# Battery_Monitoring_V3.net
KiCad netlist of a schematic drawn in EAGLE
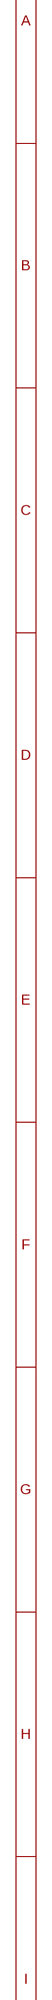
[diagram p0: schematic, sheet 1, part 1 of 2]
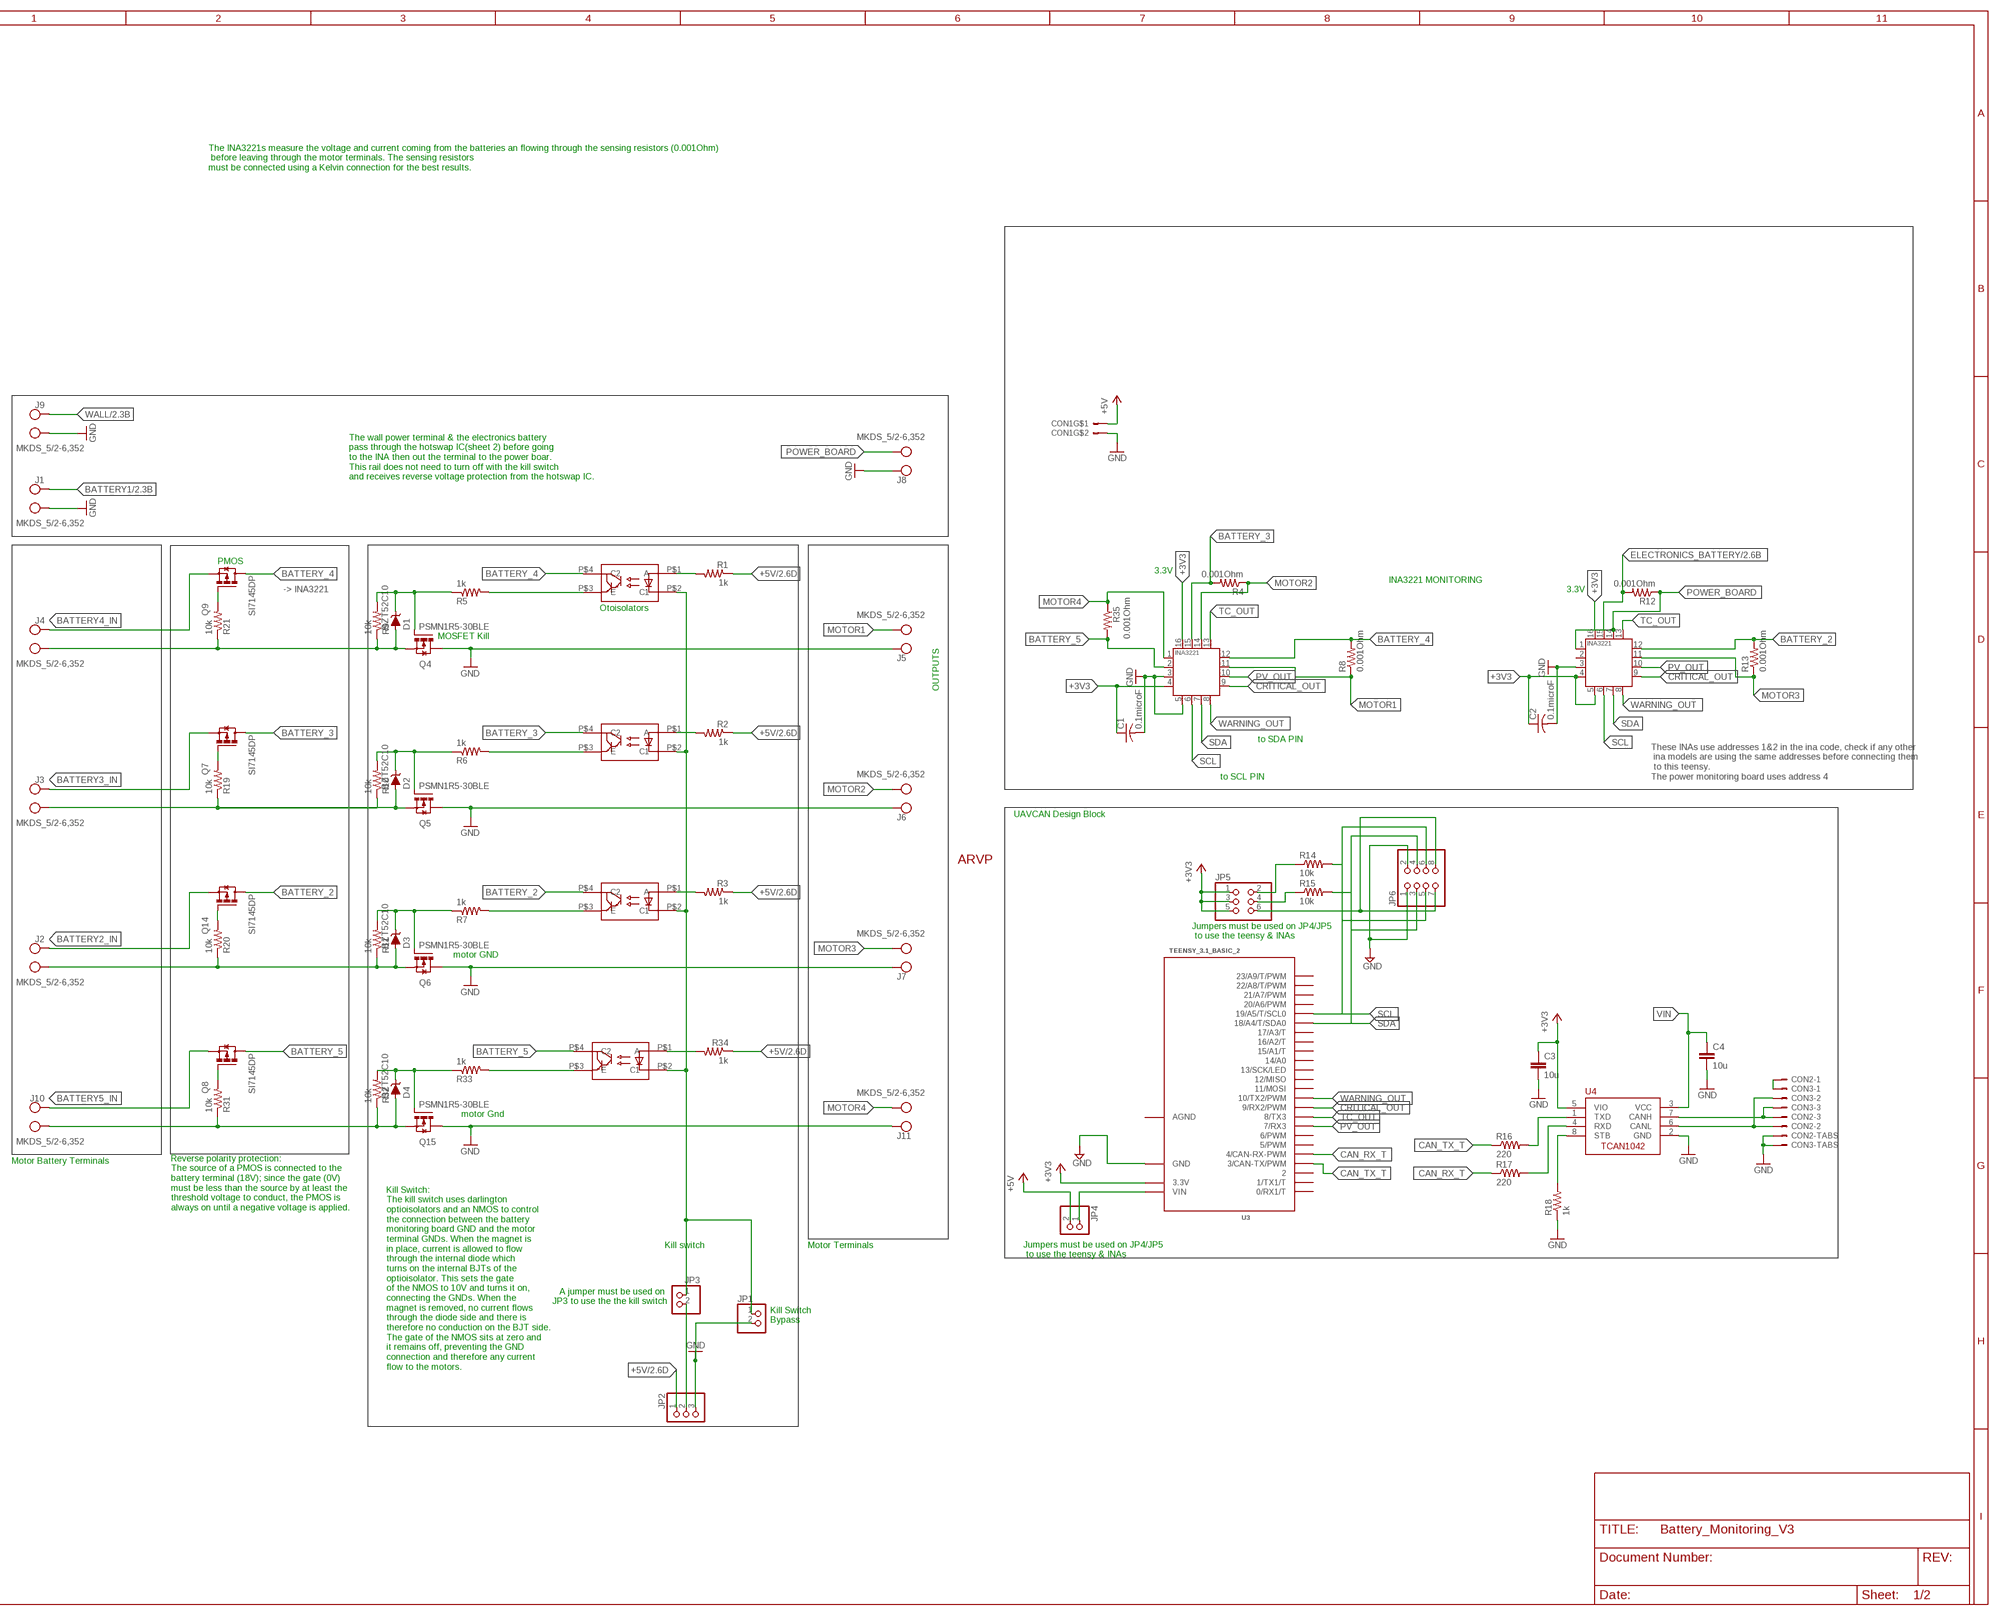
[diagram p1: schematic, sheet 1, part 2 of 2]
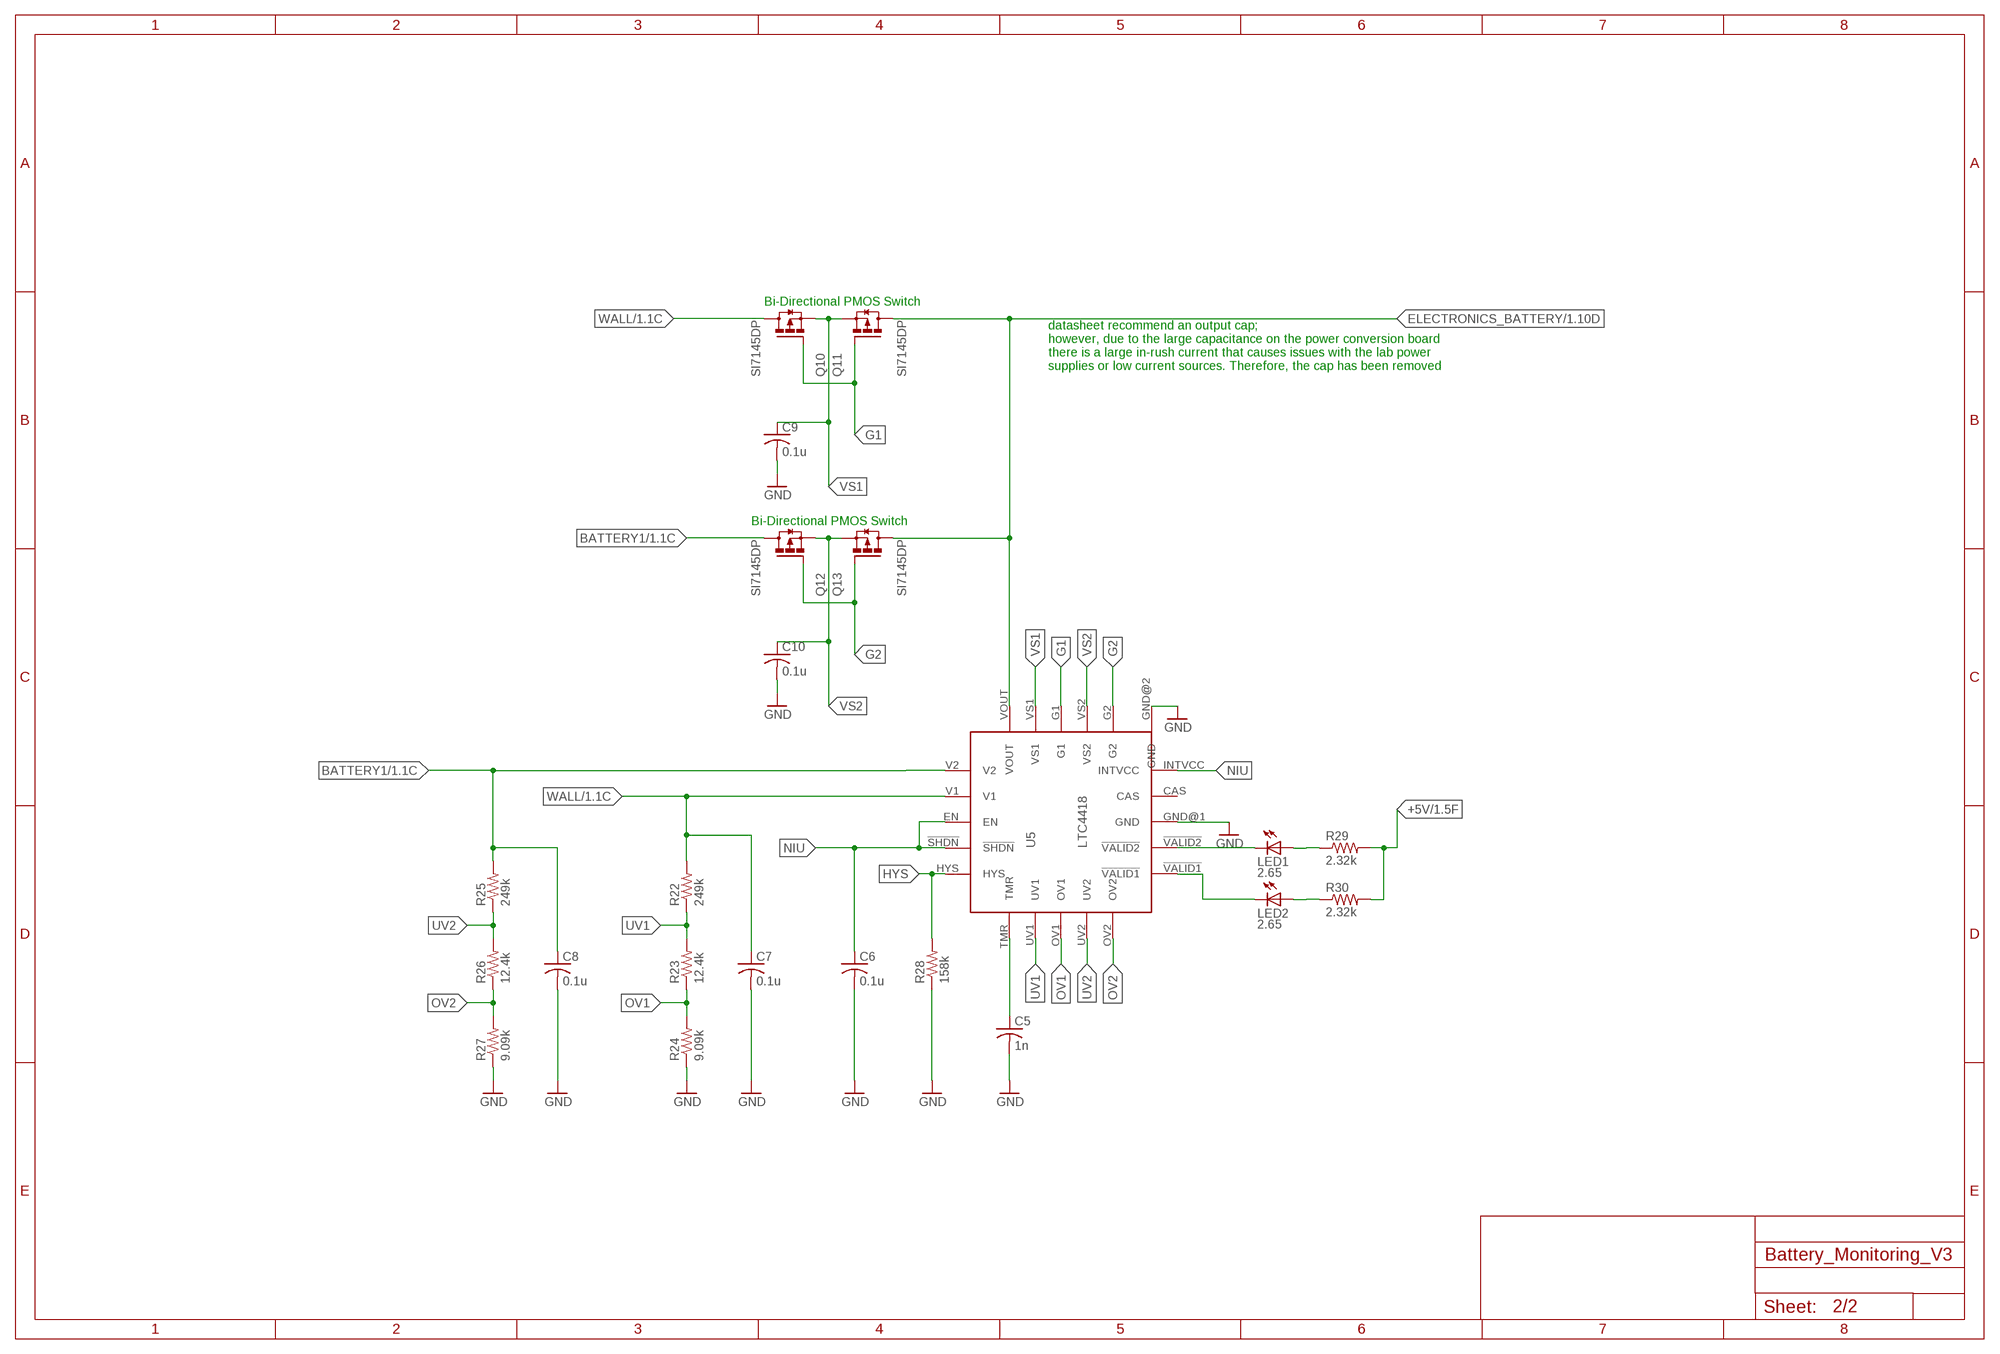
[diagram p2: schematic, sheet 2]

(export (version "E")
  (design (tool "Eeschema 10.0.6"))
  (components
    (comp (ref "ARVP1")
      (value "ARVP_LOGO")
      (footprint "eagle-import:ARVP")
      (libsource (lib "eagle-import") (part "ARVP_LOGO"))
    )
    (comp (ref "C1")
      (value "0.1microF")
      (footprint "eagle-import:C2012")
      (libsource (lib "eagle-import") (part "resistor_348_C-USC2012"))
    )
    (comp (ref "C2")
      (value "0.1microF")
      (footprint "eagle-import:C2012")
      (libsource (lib "eagle-import") (part "resistor_348_C-USC2012"))
    )
    (comp (ref "C3")
      (value "10u")
      (footprint "eagle-import:C0805")
      (libsource (lib "eagle-import") (part "C-EUC0805"))
    )
    (comp (ref "C4")
      (value "10u")
      (footprint "eagle-import:C0805")
      (libsource (lib "eagle-import") (part "C-EUC0805"))
    )
    (comp (ref "CON1")
      (value "MOLEX_5566-2")
      (footprint "eagle-import:5566-2")
      (libsource (lib "eagle-import") (part "MOLEX_5566-2"))
    )
    (comp (ref "CON2")
      (value "SM03B-GHS-TB")
      (footprint "eagle-import:SM03B-GHS-TB")
      (libsource (lib "eagle-import") (part "SM03B-GHS-TB"))
    )
    (comp (ref "CON3")
      (value "SM03B-GHS-TB")
      (footprint "eagle-import:SM03B-GHS-TB")
      (libsource (lib "eagle-import") (part "SM03B-GHS-TB"))
    )
    (comp (ref "D1")
      (value "BZT52C10")
      (footprint "eagle-import:SOD-123")
      (libsource (lib "eagle-import") (part "BZT52C10"))
    )
    (comp (ref "D2")
      (value "BZT52C10")
      (footprint "eagle-import:SOD-123")
      (libsource (lib "eagle-import") (part "BZT52C10"))
    )
    (comp (ref "D3")
      (value "BZT52C10")
      (footprint "eagle-import:SOD-123")
      (libsource (lib "eagle-import") (part "BZT52C10"))
    )
    (comp (ref "D4")
      (value "BZT52C10")
      (footprint "eagle-import:SOD-123")
      (libsource (lib "eagle-import") (part "BZT52C10"))
    )
    (comp (ref "J1")
      (value "MKDS_5/2-6,352")
      (footprint "eagle-import:MKDS_5_2-6,35")
      (libsource (lib "eagle-import") (part "MKDS_5/2-6,352"))
    )
    (comp (ref "J2")
      (value "MKDS_5/2-6,352")
      (footprint "eagle-import:MKDS_5_2-6,35")
      (libsource (lib "eagle-import") (part "MKDS_5/2-6,352"))
    )
    (comp (ref "J3")
      (value "MKDS_5/2-6,352")
      (footprint "eagle-import:MKDS_5_2-6,35")
      (libsource (lib "eagle-import") (part "MKDS_5/2-6,352"))
    )
    (comp (ref "J4")
      (value "MKDS_5/2-6,352")
      (footprint "eagle-import:MKDS_5_2-6,35")
      (libsource (lib "eagle-import") (part "MKDS_5/2-6,352"))
    )
    (comp (ref "J5")
      (value "MKDS_5/2-6,352")
      (footprint "eagle-import:MKDS_5_2-6,35")
      (libsource (lib "eagle-import") (part "MKDS_5/2-6,352"))
    )
    (comp (ref "J6")
      (value "MKDS_5/2-6,352")
      (footprint "eagle-import:MKDS_5_2-6,35")
      (libsource (lib "eagle-import") (part "MKDS_5/2-6,352"))
    )
    (comp (ref "J7")
      (value "MKDS_5/2-6,352")
      (footprint "eagle-import:MKDS_5_2-6,35")
      (libsource (lib "eagle-import") (part "MKDS_5/2-6,352"))
    )
    (comp (ref "J8")
      (value "MKDS_5/2-6,352")
      (footprint "eagle-import:MKDS_5_2-6,35")
      (libsource (lib "eagle-import") (part "MKDS_5/2-6,352"))
    )
    (comp (ref "J9")
      (value "MKDS_5/2-6,352")
      (footprint "eagle-import:MKDS_5_2-6,35")
      (libsource (lib "eagle-import") (part "MKDS_5/2-6,352"))
    )
    (comp (ref "J10")
      (value "MKDS_5/2-6,352")
      (footprint "eagle-import:MKDS_5_2-6,35")
      (libsource (lib "eagle-import") (part "MKDS_5/2-6,352"))
    )
    (comp (ref "J11")
      (value "MKDS_5/2-6,352")
      (footprint "eagle-import:MKDS_5_2-6,35")
      (libsource (lib "eagle-import") (part "MKDS_5/2-6,352"))
    )
    (comp (ref "JP1")
      (value "PINHD-1X2")
      (footprint "eagle-import:1X02")
      (libsource (lib "eagle-import") (part "PINHD-1X2"))
    )
    (comp (ref "JP2")
      (value "PINHD-1X3")
      (footprint "eagle-import:1X03")
      (libsource (lib "eagle-import") (part "PINHD-1X3"))
    )
    (comp (ref "JP3")
      (value "PINHD-1X2")
      (footprint "eagle-import:1X02")
      (libsource (lib "eagle-import") (part "PINHD-1X2"))
    )
    (comp (ref "JP4")
      (value "PINHD-1X2")
      (footprint "eagle-import:1X02")
      (libsource (lib "eagle-import") (part "PINHD-1X2"))
    )
    (comp (ref "JP5")
      (value "PINHD-2X3")
      (footprint "eagle-import:2X03")
      (libsource (lib "eagle-import") (part "PINHD-2X3"))
    )
    (comp (ref "JP6")
      (value "PINHD-2X4")
      (footprint "eagle-import:2X04")
      (libsource (lib "eagle-import") (part "PINHD-2X4"))
    )
    (comp (ref "Q1")
      (value "TCLD1000CT")
      (footprint "eagle-import:SOP-4L")
      (fields (field (name "SPICEPREFIX") "E"))
      (libsource (lib "eagle-import") (part "TCLD1000CT"))
    )
    (comp (ref "Q2")
      (value "TCLD1000CT")
      (footprint "eagle-import:SOP-4L")
      (libsource (lib "eagle-import") (part "TCLD1000CT"))
    )
    (comp (ref "Q3")
      (value "TCLD1000CT")
      (footprint "eagle-import:SOP-4L")
      (libsource (lib "eagle-import") (part "TCLD1000CT"))
    )
    (comp (ref "Q4")
      (value "PSMN1R5-30BLE")
      (footprint "eagle-import:SOT404_D2PAK")
      (libsource (lib "eagle-import") (part "PSMN1R5-30BLE"))
    )
    (comp (ref "Q5")
      (value "PSMN1R5-30BLE")
      (footprint "eagle-import:SOT404_D2PAK")
      (libsource (lib "eagle-import") (part "PSMN1R5-30BLE"))
    )
    (comp (ref "Q6")
      (value "PSMN1R5-30BLE")
      (footprint "eagle-import:SOT404_D2PAK")
      (libsource (lib "eagle-import") (part "PSMN1R5-30BLE"))
    )
    (comp (ref "Q7")
      (value "SI7145DP")
      (footprint "eagle-import:SO-8_PPAK_TEST")
      (fields (field (name "MPN") "SI7145DP-T1-GE3"))
      (libsource (lib "eagle-import") (part "Si7145DP_SI7145DP"))
    )
    (comp (ref "Q8")
      (value "SI7145DP")
      (footprint "eagle-import:SO-8_PPAK_TEST")
      (fields (field (name "MPN") "SI7145DP-T1-GE3"))
      (libsource (lib "eagle-import") (part "Si7145DP_SI7145DP"))
    )
    (comp (ref "Q9")
      (value "SI7145DP")
      (footprint "eagle-import:SO-8_PPAK_TEST")
      (fields (field (name "MPN") "SI7145DP-T1-GE3"))
      (libsource (lib "eagle-import") (part "Si7145DP_SI7145DP"))
    )
    (comp (ref "Q14")
      (value "SI7145DP")
      (footprint "eagle-import:SO-8_PPAK_TEST")
      (fields (field (name "MPN") "SI7145DP-T1-GE3"))
      (libsource (lib "eagle-import") (part "Si7145DP_SI7145DP"))
    )
    (comp (ref "Q15")
      (value "PSMN1R5-30BLE")
      (footprint "eagle-import:SOT404_D2PAK")
      (libsource (lib "eagle-import") (part "PSMN1R5-30BLE"))
    )
    (comp (ref "Q16")
      (value "TCLD1000CT")
      (footprint "eagle-import:SOP-4L")
      (libsource (lib "eagle-import") (part "TCLD1000CT"))
    )
    (comp (ref "R1")
      (value "1k")
      (footprint "eagle-import:R0805")
      (libsource (lib "eagle-import") (part "adafruit_420_R-US_R0805"))
    )
    (comp (ref "R2")
      (value "1k")
      (footprint "eagle-import:R0805")
      (libsource (lib "eagle-import") (part "adafruit_420_R-US_R0805"))
    )
    (comp (ref "R3")
      (value "1k")
      (footprint "eagle-import:R0805")
      (libsource (lib "eagle-import") (part "adafruit_420_R-US_R0805"))
    )
    (comp (ref "R4")
      (value "0.001Ohm")
      (footprint "eagle-import:3920")
      (libsource (lib "eagle-import") (part "HCS3920FT1L00"))
    )
    (comp (ref "R5")
      (value "1k")
      (footprint "eagle-import:M1206")
      (libsource (lib "eagle-import") (part "adafruit_420_R-US_M1206"))
    )
    (comp (ref "R6")
      (value "1k")
      (footprint "eagle-import:M1206")
      (libsource (lib "eagle-import") (part "adafruit_420_R-US_M1206"))
    )
    (comp (ref "R7")
      (value "1k")
      (footprint "eagle-import:M1206")
      (libsource (lib "eagle-import") (part "adafruit_420_R-US_M1206"))
    )
    (comp (ref "R8")
      (value "0.001Ohm")
      (footprint "eagle-import:3920")
      (libsource (lib "eagle-import") (part "HCS3920FT1L00"))
    )
    (comp (ref "R9")
      (value "10k")
      (footprint "eagle-import:M1206")
      (libsource (lib "eagle-import") (part "adafruit_420_R-US_M1206"))
    )
    (comp (ref "R10")
      (value "10k")
      (footprint "eagle-import:M1206")
      (libsource (lib "eagle-import") (part "adafruit_420_R-US_M1206"))
    )
    (comp (ref "R11")
      (value "10k")
      (footprint "eagle-import:M1206")
      (libsource (lib "eagle-import") (part "adafruit_420_R-US_M1206"))
    )
    (comp (ref "R12")
      (value "0.001Ohm")
      (footprint "eagle-import:3920")
      (libsource (lib "eagle-import") (part "HCS3920FT1L00"))
    )
    (comp (ref "R13")
      (value "0.001Ohm")
      (footprint "eagle-import:3920")
      (libsource (lib "eagle-import") (part "HCS3920FT1L00"))
    )
    (comp (ref "R14")
      (value "10k")
      (footprint "eagle-import:R1206")
      (libsource (lib "eagle-import") (part "rcl_334_R-US_R1206"))
    )
    (comp (ref "R15")
      (value "10k")
      (footprint "eagle-import:R1206")
      (libsource (lib "eagle-import") (part "rcl_334_R-US_R1206"))
    )
    (comp (ref "R16")
      (value "220")
      (footprint "eagle-import:R0805")
      (libsource (lib "eagle-import") (part "rcl_334_R-US_R0805"))
    )
    (comp (ref "R17")
      (value "220")
      (footprint "eagle-import:R0805")
      (libsource (lib "eagle-import") (part "rcl_334_R-US_R0805"))
    )
    (comp (ref "R18")
      (value "1k")
      (footprint "eagle-import:R0805")
      (libsource (lib "eagle-import") (part "rcl_334_R-US_R0805"))
    )
    (comp (ref "R19")
      (value "10k")
      (footprint "eagle-import:M1206")
      (fields (field (name "MPN") "RC0603FR-0710KL"))
      (libsource (lib "eagle-import") (part "R-US_M1206"))
    )
    (comp (ref "R20")
      (value "10k")
      (footprint "eagle-import:M1206")
      (fields (field (name "MPN") "RC0603FR-0710KL"))
      (libsource (lib "eagle-import") (part "R-US_M1206"))
    )
    (comp (ref "R21")
      (value "10k")
      (footprint "eagle-import:M1206")
      (fields (field (name "MPN") "RC0603FR-0710KL"))
      (libsource (lib "eagle-import") (part "adafruit_420_R-US_M1206"))
    )
    (comp (ref "R31")
      (value "10k")
      (footprint "eagle-import:M1206")
      (fields (field (name "MPN") "RC0603FR-0710KL"))
      (libsource (lib "eagle-import") (part "R-US_M1206"))
    )
    (comp (ref "R32")
      (value "10k")
      (footprint "eagle-import:M1206")
      (libsource (lib "eagle-import") (part "adafruit_420_R-US_M1206"))
    )
    (comp (ref "R33")
      (value "1k")
      (footprint "eagle-import:M1206")
      (libsource (lib "eagle-import") (part "adafruit_420_R-US_M1206"))
    )
    (comp (ref "R34")
      (value "1k")
      (footprint "eagle-import:R0805")
      (libsource (lib "eagle-import") (part "adafruit_420_R-US_R0805"))
    )
    (comp (ref "R35")
      (value "0.001Ohm")
      (footprint "eagle-import:3920")
      (libsource (lib "eagle-import") (part "HCS3920FT1L00"))
    )
    (comp (ref "U1")
      (value "INA3221.")
      (footprint "eagle-import:HVQFN16_4X4")
      (libsource (lib "eagle-import") (part "INA3221."))
    )
    (comp (ref "U2")
      (value "INA3221.")
      (footprint "eagle-import:HVQFN16_4X4")
      (libsource (lib "eagle-import") (part "INA3221."))
    )
    (comp (ref "U3")
      (value "TEENSY_3.1_BASIC_2")
      (footprint "eagle-import:TEENSY_3.1_BASIC_2")
      (libsource (lib "eagle-import") (part "TEENSY_3.1_BASIC_2"))
    )
    (comp (ref "U4")
      (value "TCAN1042HVDR")
      (footprint "eagle-import:SO-8")
      (libsource (lib "eagle-import") (part "TCAN1042HVDR"))
    )
    (comp (ref "C5")
      (value "1n")
      (footprint "eagle-import:C0805")
      (libsource (lib "eagle-import") (part "C-USC0805"))
    )
    (comp (ref "C6")
      (value "0.1u")
      (footprint "eagle-import:C0805")
      (libsource (lib "eagle-import") (part "C-USC0805"))
    )
    (comp (ref "C7")
      (value "0.1u")
      (footprint "eagle-import:C0805")
      (libsource (lib "eagle-import") (part "C-USC0805"))
    )
    (comp (ref "C8")
      (value "0.1u")
      (footprint "eagle-import:C0805")
      (libsource (lib "eagle-import") (part "C-USC0805"))
    )
    (comp (ref "C9")
      (value "0.1u")
      (footprint "eagle-import:C0805")
      (libsource (lib "eagle-import") (part "C-USC0805"))
    )
    (comp (ref "C10")
      (value "0.1u")
      (footprint "eagle-import:C0805")
      (libsource (lib "eagle-import") (part "C-USC0805"))
    )
    (comp (ref "LED1")
      (value "2.65")
      (footprint "eagle-import:SML0805")
      (libsource (lib "eagle-import") (part "LEDSML0805"))
    )
    (comp (ref "LED2")
      (value "2.65")
      (footprint "eagle-import:SML0805")
      (libsource (lib "eagle-import") (part "LEDSML0805"))
    )
    (comp (ref "Q10")
      (value "SI7145DP")
      (footprint "eagle-import:SO-8_PPAK_TEST")
      (libsource (lib "eagle-import") (part "SI7145DP"))
    )
    (comp (ref "Q11")
      (value "SI7145DP")
      (footprint "eagle-import:SO-8_PPAK_TEST")
      (libsource (lib "eagle-import") (part "SI7145DP"))
    )
    (comp (ref "Q12")
      (value "SI7145DP")
      (footprint "eagle-import:SO-8_PPAK_TEST")
      (libsource (lib "eagle-import") (part "SI7145DP"))
    )
    (comp (ref "Q13")
      (value "SI7145DP")
      (footprint "eagle-import:SO-8_PPAK_TEST")
      (libsource (lib "eagle-import") (part "SI7145DP"))
    )
    (comp (ref "R22")
      (value "249k")
      (footprint "eagle-import:R1206")
      (libsource (lib "eagle-import") (part "adafruit_420_R-US_R1206"))
    )
    (comp (ref "R23")
      (value "12.4k")
      (footprint "eagle-import:R0805")
      (libsource (lib "eagle-import") (part "adafruit_420_R-US_R0805"))
    )
    (comp (ref "R24")
      (value "9.09k")
      (footprint "eagle-import:R0805")
      (libsource (lib "eagle-import") (part "adafruit_420_R-US_R0805"))
    )
    (comp (ref "R25")
      (value "249k")
      (footprint "eagle-import:R1206")
      (libsource (lib "eagle-import") (part "adafruit_420_R-US_R1206"))
    )
    (comp (ref "R26")
      (value "12.4k")
      (footprint "eagle-import:R0805")
      (libsource (lib "eagle-import") (part "adafruit_420_R-US_R0805"))
    )
    (comp (ref "R27")
      (value "9.09k")
      (footprint "eagle-import:R0805")
      (libsource (lib "eagle-import") (part "adafruit_420_R-US_R0805"))
    )
    (comp (ref "R28")
      (value "158k")
      (footprint "eagle-import:R0805")
      (libsource (lib "eagle-import") (part "adafruit_420_R-US_R0805"))
    )
    (comp (ref "R29")
      (value "2.32k")
      (footprint "eagle-import:R0805")
      (libsource (lib "eagle-import") (part "adafruit_420_R-US_R0805"))
    )
    (comp (ref "R30")
      (value "2.32k")
      (footprint "eagle-import:R0805")
      (libsource (lib "eagle-import") (part "adafruit_420_R-US_R0805"))
    )
    (comp (ref "U5")
      (value "LTC4418")
      (footprint "eagle-import:20-QFN(4X4)")
      (libsource (lib "eagle-import") (part "LTC4418"))
    )
  )
  (nets
    (net (code "1") (name "+3V3") (class "Default")
      (node (ref "C1") (pin "1") (pinfunction "1_1") (pintype "passive"))
      (node (ref "C2") (pin "1") (pinfunction "1_1") (pintype "passive"))
      (node (ref "C3") (pin "1") (pinfunction "1_1") (pintype "passive"))
      (node (ref "JP5") (pin "1") (pinfunction "1_1") (pintype "passive"))
      (node (ref "JP5") (pin "3") (pinfunction "3_3") (pintype "passive"))
      (node (ref "JP5") (pin "5") (pinfunction "5_5") (pintype "passive"))
      (node (ref "U1") (pin "16") (pinfunction "VPU_16") (pintype "input"))
      (node (ref "U1") (pin "4") (pinfunction "VS_4") (pintype "power_in"))
      (node (ref "U2") (pin "16") (pinfunction "VPU_16") (pintype "input"))
      (node (ref "U2") (pin "4") (pinfunction "VS_4") (pintype "power_in"))
      (node (ref "U2") (pin "5") (pinfunction "A0_5") (pintype "input"))
      (node (ref "U3") (pin "3.3V") (pinfunction "3.3V_3.3V") (pintype "power_in"))
      (node (ref "U4") (pin "5") (pinfunction "VIO_5") (pintype "bidirectional"))
    )
    (net (code "2") (name "+5V") (class "Default")
      (node (ref "CON1") (pin "1") (pinfunction "S_1") (pintype "passive"))
      (node (ref "JP2") (pin "1") (pinfunction "1_1") (pintype "passive"))
      (node (ref "JP4") (pin "2") (pinfunction "2_2") (pintype "passive"))
      (node (ref "R1") (pin "1") (pinfunction "1_1") (pintype "passive"))
      (node (ref "R2") (pin "1") (pinfunction "1_1") (pintype "passive"))
      (node (ref "R29") (pin "2") (pinfunction "2_2") (pintype "passive"))
      (node (ref "R3") (pin "1") (pinfunction "1_1") (pintype "passive"))
      (node (ref "R30") (pin "2") (pinfunction "2_2") (pintype "passive"))
      (node (ref "R34") (pin "1") (pinfunction "1_1") (pintype "passive"))
    )
    (net (code "3") (name "AGND") (class "Default")
      (node (ref "U3") (pin "AGND") (pinfunction "AGND_AGND") (pintype "power_in"))
    )
    (net (code "4") (name "BATTERY1") (class "Default")
      (node (ref "C8") (pin "1") (pinfunction "1_1") (pintype "passive"))
      (node (ref "J1") (pin "2") (pinfunction "KL1_2") (pintype "passive"))
      (node (ref "Q12") (pin "D@1") (pinfunction "D_D@1") (pintype "passive"))
      (node (ref "Q12") (pin "D@2") (pinfunction "D_D@2") (pintype "passive"))
      (node (ref "Q12") (pin "D@3") (pinfunction "D_D@3") (pintype "passive"))
      (node (ref "Q12") (pin "D@4") (pinfunction "D_D@4") (pintype "passive"))
      (node (ref "Q12") (pin "D@5") (pinfunction "D_D@5") (pintype "passive"))
      (node (ref "R25") (pin "2") (pinfunction "2_2") (pintype "passive"))
      (node (ref "U5") (pin "V2") (pinfunction "V2_V2") (pintype "bidirectional"))
    )
    (net (code "5") (name "BATTERY2_IN") (class "Default")
      (node (ref "J2") (pin "2") (pinfunction "KL1_2") (pintype "passive"))
      (node (ref "Q14") (pin "S@1") (pinfunction "S_S@1") (pintype "passive"))
      (node (ref "Q14") (pin "S@2") (pinfunction "S_S@2") (pintype "passive"))
      (node (ref "Q14") (pin "S@3") (pinfunction "S_S@3") (pintype "passive"))
    )
    (net (code "6") (name "BATTERY3_IN") (class "Default")
      (node (ref "J3") (pin "2") (pinfunction "KL1_2") (pintype "passive"))
      (node (ref "Q7") (pin "S@1") (pinfunction "S_S@1") (pintype "passive"))
      (node (ref "Q7") (pin "S@2") (pinfunction "S_S@2") (pintype "passive"))
      (node (ref "Q7") (pin "S@3") (pinfunction "S_S@3") (pintype "passive"))
    )
    (net (code "7") (name "BATTERY4_IN") (class "Default")
      (node (ref "J4") (pin "2") (pinfunction "KL1_2") (pintype "passive"))
      (node (ref "Q9") (pin "S@1") (pinfunction "S_S@1") (pintype "passive"))
      (node (ref "Q9") (pin "S@2") (pinfunction "S_S@2") (pintype "passive"))
      (node (ref "Q9") (pin "S@3") (pinfunction "S_S@3") (pintype "passive"))
    )
    (net (code "8") (name "BATTERY5_IN") (class "Default")
      (node (ref "J10") (pin "2") (pinfunction "KL1_2") (pintype "passive"))
      (node (ref "Q8") (pin "S@1") (pinfunction "S_S@1") (pintype "passive"))
      (node (ref "Q8") (pin "S@2") (pinfunction "S_S@2") (pintype "passive"))
      (node (ref "Q8") (pin "S@3") (pinfunction "S_S@3") (pintype "passive"))
    )
    (net (code "9") (name "BATTERY_2") (class "Default")
      (node (ref "Q14") (pin "D@1") (pinfunction "D_D@1") (pintype "passive"))
      (node (ref "Q14") (pin "D@2") (pinfunction "D_D@2") (pintype "passive"))
      (node (ref "Q14") (pin "D@3") (pinfunction "D_D@3") (pintype "passive"))
      (node (ref "Q14") (pin "D@4") (pinfunction "D_D@4") (pintype "passive"))
      (node (ref "Q14") (pin "D@5") (pinfunction "D_D@5") (pintype "passive"))
      (node (ref "Q3") (pin "P$4") (pinfunction "C2_P$4") (pintype "bidirectional"))
      (node (ref "R13") (pin "P$2") (pinfunction "2_P$2") (pintype "passive"))
      (node (ref "U2") (pin "12") (pinfunction "IN+1_12") (pintype "input"))
    )
    (net (code "10") (name "BATTERY_3") (class "Default")
      (node (ref "Q2") (pin "P$4") (pinfunction "C2_P$4") (pintype "bidirectional"))
      (node (ref "Q7") (pin "D@1") (pinfunction "D_D@1") (pintype "passive"))
      (node (ref "Q7") (pin "D@2") (pinfunction "D_D@2") (pintype "passive"))
      (node (ref "Q7") (pin "D@3") (pinfunction "D_D@3") (pintype "passive"))
      (node (ref "Q7") (pin "D@4") (pinfunction "D_D@4") (pintype "passive"))
      (node (ref "Q7") (pin "D@5") (pinfunction "D_D@5") (pintype "passive"))
      (node (ref "R4") (pin "P$2") (pinfunction "2_P$2") (pintype "passive"))
      (node (ref "U1") (pin "15") (pinfunction "IN+2_15") (pintype "input"))
    )
    (net (code "11") (name "BATTERY_4") (class "Default")
      (node (ref "Q1") (pin "P$4") (pinfunction "C2_P$4") (pintype "bidirectional"))
      (node (ref "Q9") (pin "D@1") (pinfunction "D_D@1") (pintype "passive"))
      (node (ref "Q9") (pin "D@2") (pinfunction "D_D@2") (pintype "passive"))
      (node (ref "Q9") (pin "D@3") (pinfunction "D_D@3") (pintype "passive"))
      (node (ref "Q9") (pin "D@4") (pinfunction "D_D@4") (pintype "passive"))
      (node (ref "Q9") (pin "D@5") (pinfunction "D_D@5") (pintype "passive"))
      (node (ref "R8") (pin "P$2") (pinfunction "2_P$2") (pintype "passive"))
      (node (ref "U1") (pin "12") (pinfunction "IN+1_12") (pintype "input"))
    )
    (net (code "12") (name "BATTERY_5") (class "Default")
      (node (ref "Q16") (pin "P$4") (pinfunction "C2_P$4") (pintype "bidirectional"))
      (node (ref "Q8") (pin "D@1") (pinfunction "D_D@1") (pintype "passive"))
      (node (ref "Q8") (pin "D@2") (pinfunction "D_D@2") (pintype "passive"))
      (node (ref "Q8") (pin "D@3") (pinfunction "D_D@3") (pintype "passive"))
      (node (ref "Q8") (pin "D@4") (pinfunction "D_D@4") (pintype "passive"))
      (node (ref "Q8") (pin "D@5") (pinfunction "D_D@5") (pintype "passive"))
      (node (ref "R35") (pin "P$2") (pinfunction "2_P$2") (pintype "passive"))
      (node (ref "U1") (pin "2") (pinfunction "IN+3_2") (pintype "input"))
    )
    (net (code "13") (name "CAN_RX_T") (class "Default")
      (node (ref "R17") (pin "1") (pinfunction "1_1") (pintype "passive"))
      (node (ref "U3") (pin "4") (pinfunction "4/CAN-RX-PWM_4") (pintype "bidirectional"))
    )
    (net (code "14") (name "CAN_TX_T") (class "Default")
      (node (ref "R16") (pin "1") (pinfunction "1_1") (pintype "passive"))
      (node (ref "U3") (pin "3") (pinfunction "3/CAN-TX/PWM_3") (pintype "bidirectional"))
    )
    (net (code "15") (name "CRITICAL_OUT") (class "Default")
      (node (ref "U1") (pin "9") (pinfunction "CRITICAL_9") (pintype "output"))
      (node (ref "U2") (pin "9") (pinfunction "CRITICAL_9") (pintype "output"))
      (node (ref "U3") (pin "9") (pinfunction "9/RX2/PWM_9") (pintype "bidirectional"))
    )
    (net (code "16") (name "ELECTRONICS_BATTERY") (class "Default")
      (node (ref "Q11") (pin "D@1") (pinfunction "D_D@1") (pintype "passive"))
      (node (ref "Q11") (pin "D@2") (pinfunction "D_D@2") (pintype "passive"))
      (node (ref "Q11") (pin "D@3") (pinfunction "D_D@3") (pintype "passive"))
      (node (ref "Q11") (pin "D@4") (pinfunction "D_D@4") (pintype "passive"))
      (node (ref "Q11") (pin "D@5") (pinfunction "D_D@5") (pintype "passive"))
      (node (ref "Q13") (pin "D@1") (pinfunction "D_D@1") (pintype "passive"))
      (node (ref "Q13") (pin "D@2") (pinfunction "D_D@2") (pintype "passive"))
      (node (ref "Q13") (pin "D@3") (pinfunction "D_D@3") (pintype "passive"))
      (node (ref "Q13") (pin "D@4") (pinfunction "D_D@4") (pintype "passive"))
      (node (ref "Q13") (pin "D@5") (pinfunction "D_D@5") (pintype "passive"))
      (node (ref "R12") (pin "P$2") (pinfunction "2_P$2") (pintype "passive"))
      (node (ref "U2") (pin "15") (pinfunction "IN+2_15") (pintype "input"))
      (node (ref "U5") (pin "VOUT") (pinfunction "VOUT_VOUT") (pintype "power_in"))
    )
    (net (code "17") (name "G1") (class "Default")
      (node (ref "Q10") (pin "G") (pinfunction "G_G") (pintype "passive"))
      (node (ref "Q11") (pin "G") (pinfunction "G_G") (pintype "passive"))
      (node (ref "U5") (pin "G1") (pinfunction "G1_G1") (pintype "bidirectional"))
    )
    (net (code "18") (name "G2") (class "Default")
      (node (ref "Q12") (pin "G") (pinfunction "G_G") (pintype "passive"))
      (node (ref "Q13") (pin "G") (pinfunction "G_G") (pintype "passive"))
      (node (ref "U5") (pin "G2") (pinfunction "G2_G2") (pintype "bidirectional"))
    )
    (net (code "19") (name "GND") (class "Default")
      (node (ref "C1") (pin "2") (pinfunction "2_2") (pintype "passive"))
      (node (ref "C10") (pin "2") (pinfunction "2_2") (pintype "passive"))
      (node (ref "C2") (pin "2") (pinfunction "2_2") (pintype "passive"))
      (node (ref "C3") (pin "2") (pinfunction "2_2") (pintype "passive"))
      (node (ref "C4") (pin "2") (pinfunction "2_2") (pintype "passive"))
      (node (ref "C5") (pin "2") (pinfunction "2_2") (pintype "passive"))
      (node (ref "C6") (pin "2") (pinfunction "2_2") (pintype "passive"))
      (node (ref "C7") (pin "2") (pinfunction "2_2") (pintype "passive"))
      (node (ref "C8") (pin "2") (pinfunction "2_2") (pintype "passive"))
      (node (ref "C9") (pin "2") (pinfunction "2_2") (pintype "passive"))
      (node (ref "CON1") (pin "2") (pinfunction "S_2") (pintype "passive"))
      (node (ref "CON2") (pin "P$4") (pinfunction "S_P$4") (pintype "passive"))
      (node (ref "CON2") (pin "P$5") (pinfunction "S_P$5") (pintype "passive"))
      (node (ref "CON3") (pin "P$4") (pinfunction "S_P$4") (pintype "passive"))
      (node (ref "CON3") (pin "P$5") (pinfunction "S_P$5") (pintype "passive"))
      (node (ref "J1") (pin "1") (pinfunction "KL_1") (pintype "passive"))
      (node (ref "J11") (pin "2") (pinfunction "KL1_2") (pintype "passive"))
      (node (ref "J5") (pin "2") (pinfunction "KL1_2") (pintype "passive"))
      (node (ref "J6") (pin "2") (pinfunction "KL1_2") (pintype "passive"))
      (node (ref "J7") (pin "2") (pinfunction "KL1_2") (pintype "passive"))
      (node (ref "J8") (pin "2") (pinfunction "KL1_2") (pintype "passive"))
      (node (ref "J9") (pin "1") (pinfunction "KL_1") (pintype "passive"))
      (node (ref "JP1") (pin "2") (pinfunction "2_2") (pintype "passive"))
      (node (ref "JP2") (pin "3") (pinfunction "3_3") (pintype "passive"))
      (node (ref "JP6") (pin "1") (pinfunction "1_1") (pintype "passive"))
      (node (ref "JP6") (pin "2") (pinfunction "2_2") (pintype "passive"))
      (node (ref "Q15") (pin "2D") (pinfunction "D_2D") (pintype "passive"))
      (node (ref "Q4") (pin "2D") (pinfunction "D_2D") (pintype "passive"))
      (node (ref "Q5") (pin "2D") (pinfunction "D_2D") (pintype "passive"))
      (node (ref "Q6") (pin "2D") (pinfunction "D_2D") (pintype "passive"))
      (node (ref "R18") (pin "1") (pinfunction "1_1") (pintype "passive"))
      (node (ref "R24") (pin "1") (pinfunction "1_1") (pintype "passive"))
      (node (ref "R27") (pin "1") (pinfunction "1_1") (pintype "passive"))
      (node (ref "R28") (pin "1") (pinfunction "1_1") (pintype "passive"))
      (node (ref "U1") (pin "3") (pinfunction "GND_3") (pintype "power_in"))
      (node (ref "U1") (pin "5") (pinfunction "A0_5") (pintype "input"))
      (node (ref "U2") (pin "3") (pinfunction "GND_3") (pintype "power_in"))
      (node (ref "U3") (pin "GND") (pinfunction "GND_GND") (pintype "power_in"))
      (node (ref "U4") (pin "2") (pinfunction "GND_2") (pintype "bidirectional"))
      (node (ref "U5") (pin "GND@1") (pinfunction "GND_GND@1") (pintype "power_in"))
      (node (ref "U5") (pin "GND@2") (pinfunction "GND_GND@2") (pintype "power_in"))
    )
    (net (code "20") (name "HYS") (class "Default")
      (node (ref "R28") (pin "2") (pinfunction "2_2") (pintype "passive"))
      (node (ref "U5") (pin "HYS") (pinfunction "HYS_HYS") (pintype "bidirectional"))
    )
    (net (code "21") (name "MOTOR1") (class "Default")
      (node (ref "J5") (pin "1") (pinfunction "KL_1") (pintype "passive"))
      (node (ref "R8") (pin "P$1") (pinfunction "1_P$1") (pintype "passive"))
      (node (ref "U1") (pin "11") (pinfunction "IN-1_11") (pintype "input"))
    )
    (net (code "22") (name "MOTOR2") (class "Default")
      (node (ref "J6") (pin "1") (pinfunction "KL_1") (pintype "passive"))
      (node (ref "R4") (pin "P$1") (pinfunction "1_P$1") (pintype "passive"))
      (node (ref "U1") (pin "14") (pinfunction "IN-2_14") (pintype "input"))
    )
    (net (code "23") (name "MOTOR3") (class "Default")
      (node (ref "J7") (pin "1") (pinfunction "KL_1") (pintype "passive"))
      (node (ref "R13") (pin "P$1") (pinfunction "1_P$1") (pintype "passive"))
      (node (ref "U2") (pin "11") (pinfunction "IN-1_11") (pintype "input"))
    )
    (net (code "24") (name "MOTOR4") (class "Default")
      (node (ref "J11") (pin "1") (pinfunction "KL_1") (pintype "passive"))
      (node (ref "R35") (pin "P$1") (pinfunction "1_P$1") (pintype "passive"))
      (node (ref "U1") (pin "1") (pinfunction "IN-3_1") (pintype "input"))
    )
    (net (code "25") (name "NIU") (class "Default")
      (node (ref "C6") (pin "1") (pinfunction "1_1") (pintype "passive"))
      (node (ref "U5") (pin "!SHDN") (pinfunction "~{SHDN}_!SHDN") (pintype "bidirectional"))
      (node (ref "U5") (pin "EN") (pinfunction "EN_EN") (pintype "bidirectional"))
      (node (ref "U5") (pin "INTVCC") (pinfunction "INTVCC_INTVCC") (pintype "bidirectional"))
    )
    (net (code "26") (name "Net-(C5-Pad1)") (class "Default")
      (node (ref "C5") (pin "1") (pinfunction "1_1") (pintype "passive"))
      (node (ref "U5") (pin "TMR") (pinfunction "TMR_TMR") (pintype "bidirectional"))
    )
    (net (code "27") (name "Net-(CON2A-S)") (class "Default")
      (node (ref "CON2") (pin "P$1") (pinfunction "S_P$1") (pintype "passive"))
      (node (ref "CON3") (pin "P$1") (pinfunction "S_P$1") (pintype "passive"))
    )
    (net (code "28") (name "Net-(CON2B-S)") (class "Default")
      (node (ref "CON2") (pin "P$2") (pinfunction "S_P$2") (pintype "passive"))
      (node (ref "CON3") (pin "P$2") (pinfunction "S_P$2") (pintype "passive"))
      (node (ref "U4") (pin "6") (pinfunction "CANL_6") (pintype "bidirectional"))
    )
    (net (code "29") (name "Net-(CON2C-S)") (class "Default")
      (node (ref "CON2") (pin "P$3") (pinfunction "S_P$3") (pintype "passive"))
      (node (ref "CON3") (pin "P$3") (pinfunction "S_P$3") (pintype "passive"))
      (node (ref "U4") (pin "7") (pinfunction "CANH_7") (pintype "bidirectional"))
    )
    (net (code "30") (name "Net-(D1-A)") (class "Default")
      (node (ref "D1") (pin "P$2") (pinfunction "A_P$2") (pintype "passive"))
      (node (ref "J4") (pin "1") (pinfunction "KL_1") (pintype "passive"))
      (node (ref "Q4") (pin "3S") (pinfunction "S_3S") (pintype "passive"))
      (node (ref "R21") (pin "1") (pinfunction "1_1") (pintype "passive"))
      (node (ref "R9") (pin "1") (pinfunction "1_1") (pintype "passive"))
    )
    (net (code "31") (name "Net-(D1-C)") (class "Default")
      (node (ref "D1") (pin "P$1") (pinfunction "C_P$1") (pintype "passive"))
      (node (ref "Q4") (pin "1G") (pinfunction "G_1G") (pintype "passive"))
      (node (ref "R5") (pin "1") (pinfunction "1_1") (pintype "passive"))
      (node (ref "R9") (pin "2") (pinfunction "2_2") (pintype "passive"))
    )
    (net (code "32") (name "Net-(D2-A)") (class "Default")
      (node (ref "D2") (pin "P$2") (pinfunction "A_P$2") (pintype "passive"))
      (node (ref "J3") (pin "1") (pinfunction "KL_1") (pintype "passive"))
      (node (ref "Q5") (pin "3S") (pinfunction "S_3S") (pintype "passive"))
      (node (ref "R10") (pin "1") (pinfunction "1_1") (pintype "passive"))
      (node (ref "R19") (pin "1") (pinfunction "1_1") (pintype "passive"))
    )
    (net (code "33") (name "Net-(D2-C)") (class "Default")
      (node (ref "D2") (pin "P$1") (pinfunction "C_P$1") (pintype "passive"))
      (node (ref "Q5") (pin "1G") (pinfunction "G_1G") (pintype "passive"))
      (node (ref "R10") (pin "2") (pinfunction "2_2") (pintype "passive"))
      (node (ref "R6") (pin "1") (pinfunction "1_1") (pintype "passive"))
    )
    (net (code "34") (name "Net-(D3-A)") (class "Default")
      (node (ref "D3") (pin "P$2") (pinfunction "A_P$2") (pintype "passive"))
      (node (ref "J2") (pin "1") (pinfunction "KL_1") (pintype "passive"))
      (node (ref "Q6") (pin "3S") (pinfunction "S_3S") (pintype "passive"))
      (node (ref "R11") (pin "1") (pinfunction "1_1") (pintype "passive"))
      (node (ref "R20") (pin "1") (pinfunction "1_1") (pintype "passive"))
    )
    (net (code "35") (name "Net-(D3-C)") (class "Default")
      (node (ref "D3") (pin "P$1") (pinfunction "C_P$1") (pintype "passive"))
      (node (ref "Q6") (pin "1G") (pinfunction "G_1G") (pintype "passive"))
      (node (ref "R11") (pin "2") (pinfunction "2_2") (pintype "passive"))
      (node (ref "R7") (pin "1") (pinfunction "1_1") (pintype "passive"))
    )
    (net (code "36") (name "Net-(D4-A)") (class "Default")
      (node (ref "D4") (pin "P$2") (pinfunction "A_P$2") (pintype "passive"))
      (node (ref "J10") (pin "1") (pinfunction "KL_1") (pintype "passive"))
      (node (ref "Q15") (pin "3S") (pinfunction "S_3S") (pintype "passive"))
      (node (ref "R31") (pin "1") (pinfunction "1_1") (pintype "passive"))
      (node (ref "R32") (pin "1") (pinfunction "1_1") (pintype "passive"))
    )
    (net (code "37") (name "Net-(D4-C)") (class "Default")
      (node (ref "D4") (pin "P$1") (pinfunction "C_P$1") (pintype "passive"))
      (node (ref "Q15") (pin "1G") (pinfunction "G_1G") (pintype "passive"))
      (node (ref "R32") (pin "2") (pinfunction "2_2") (pintype "passive"))
      (node (ref "R33") (pin "1") (pinfunction "1_1") (pintype "passive"))
    )
    (net (code "38") (name "Net-(JP2-Pad2)") (class "Default")
      (node (ref "JP2") (pin "2") (pinfunction "2_2") (pintype "passive"))
      (node (ref "JP3") (pin "2") (pinfunction "2_2") (pintype "passive"))
    )
    (net (code "39") (name "Net-(JP5-Pad2)") (class "Default")
      (node (ref "JP5") (pin "2") (pinfunction "2_2") (pintype "passive"))
      (node (ref "R14") (pin "1") (pinfunction "1_1") (pintype "passive"))
    )
    (net (code "40") (name "Net-(JP5-Pad4)") (class "Default")
      (node (ref "JP5") (pin "4") (pinfunction "4_4") (pintype "passive"))
      (node (ref "R15") (pin "1") (pinfunction "1_1") (pintype "passive"))
    )
    (net (code "41") (name "Net-(JP5-Pad6)") (class "Default")
      (node (ref "JP5") (pin "6") (pinfunction "6_6") (pintype "passive"))
      (node (ref "JP6") (pin "7") (pinfunction "7_7") (pintype "passive"))
      (node (ref "JP6") (pin "8") (pinfunction "8_8") (pintype "passive"))
    )
    (net (code "42") (name "Net-(LED1-PadA)") (class "Default")
      (node (ref "LED1") (pin "A") (pinfunction "A_A") (pintype "passive"))
      (node (ref "R29") (pin "1") (pinfunction "1_1") (pintype "passive"))
    )
    (net (code "43") (name "Net-(LED2-PadA)") (class "Default")
      (node (ref "LED2") (pin "A") (pinfunction "A_A") (pintype "passive"))
      (node (ref "R30") (pin "1") (pinfunction "1_1") (pintype "passive"))
    )
    (net (code "44") (name "Net-(Q1-A)") (class "Default")
      (node (ref "Q1") (pin "P$1") (pinfunction "A_P$1") (pintype "bidirectional"))
      (node (ref "R1") (pin "2") (pinfunction "2_2") (pintype "passive"))
    )
    (net (code "45") (name "Net-(Q1-C1)") (class "Default")
      (node (ref "JP1") (pin "1") (pinfunction "1_1") (pintype "passive"))
      (node (ref "JP3") (pin "1") (pinfunction "1_1") (pintype "passive"))
      (node (ref "Q1") (pin "P$2") (pinfunction "C1_P$2") (pintype "bidirectional"))
      (node (ref "Q16") (pin "P$2") (pinfunction "C1_P$2") (pintype "bidirectional"))
      (node (ref "Q2") (pin "P$2") (pinfunction "C1_P$2") (pintype "bidirectional"))
      (node (ref "Q3") (pin "P$2") (pinfunction "C1_P$2") (pintype "bidirectional"))
    )
    (net (code "46") (name "Net-(Q1-E)") (class "Default")
      (node (ref "Q1") (pin "P$3") (pinfunction "E_P$3") (pintype "bidirectional"))
      (node (ref "R5") (pin "2") (pinfunction "2_2") (pintype "passive"))
    )
    (net (code "47") (name "Net-(Q2-A)") (class "Default")
      (node (ref "Q2") (pin "P$1") (pinfunction "A_P$1") (pintype "bidirectional"))
      (node (ref "R2") (pin "2") (pinfunction "2_2") (pintype "passive"))
    )
    (net (code "48") (name "Net-(Q2-E)") (class "Default")
      (node (ref "Q2") (pin "P$3") (pinfunction "E_P$3") (pintype "bidirectional"))
      (node (ref "R6") (pin "2") (pinfunction "2_2") (pintype "passive"))
    )
    (net (code "49") (name "Net-(Q3-A)") (class "Default")
      (node (ref "Q3") (pin "P$1") (pinfunction "A_P$1") (pintype "bidirectional"))
      (node (ref "R3") (pin "2") (pinfunction "2_2") (pintype "passive"))
    )
    (net (code "50") (name "Net-(Q3-E)") (class "Default")
      (node (ref "Q3") (pin "P$3") (pinfunction "E_P$3") (pintype "bidirectional"))
      (node (ref "R7") (pin "2") (pinfunction "2_2") (pintype "passive"))
    )
    (net (code "51") (name "Net-(Q7-PadG)") (class "Default")
      (node (ref "Q7") (pin "G") (pinfunction "G_G") (pintype "passive"))
      (node (ref "R19") (pin "2") (pinfunction "2_2") (pintype "passive"))
    )
    (net (code "52") (name "Net-(Q8-PadG)") (class "Default")
      (node (ref "Q8") (pin "G") (pinfunction "G_G") (pintype "passive"))
      (node (ref "R31") (pin "2") (pinfunction "2_2") (pintype "passive"))
    )
    (net (code "53") (name "Net-(Q9-PadG)") (class "Default")
      (node (ref "Q9") (pin "G") (pinfunction "G_G") (pintype "passive"))
      (node (ref "R21") (pin "2") (pinfunction "2_2") (pintype "passive"))
    )
    (net (code "54") (name "Net-(Q14-PadG)") (class "Default")
      (node (ref "Q14") (pin "G") (pinfunction "G_G") (pintype "passive"))
      (node (ref "R20") (pin "2") (pinfunction "2_2") (pintype "passive"))
    )
    (net (code "55") (name "Net-(Q16-A)") (class "Default")
      (node (ref "Q16") (pin "P$1") (pinfunction "A_P$1") (pintype "bidirectional"))
      (node (ref "R34") (pin "2") (pinfunction "2_2") (pintype "passive"))
    )
    (net (code "56") (name "Net-(Q16-E)") (class "Default")
      (node (ref "Q16") (pin "P$3") (pinfunction "E_P$3") (pintype "bidirectional"))
      (node (ref "R33") (pin "2") (pinfunction "2_2") (pintype "passive"))
    )
    (net (code "57") (name "Net-(U4-RXD)") (class "Default")
      (node (ref "R17") (pin "2") (pinfunction "2_2") (pintype "passive"))
      (node (ref "U4") (pin "4") (pinfunction "RXD_4") (pintype "bidirectional"))
    )
    (net (code "58") (name "Net-(U4-STB)") (class "Default")
      (node (ref "R18") (pin "2") (pinfunction "2_2") (pintype "passive"))
      (node (ref "U4") (pin "8") (pinfunction "STB_8") (pintype "bidirectional"))
    )
    (net (code "59") (name "Net-(U4-TXD)") (class "Default")
      (node (ref "R16") (pin "2") (pinfunction "2_2") (pintype "passive"))
      (node (ref "U4") (pin "1") (pinfunction "TXD_1") (pintype "bidirectional"))
    )
    (net (code "60") (name "Net-(U5-~{VALID1})") (class "Default")
      (node (ref "LED2") (pin "C") (pinfunction "C_C") (pintype "passive"))
      (node (ref "U5") (pin "!VALID1") (pinfunction "~{VALID1}_!VALID1") (pintype "bidirectional"))
    )
    (net (code "61") (name "Net-(U5-~{VALID2})") (class "Default")
      (node (ref "LED1") (pin "C") (pinfunction "C_C") (pintype "passive"))
      (node (ref "U5") (pin "!VALID2") (pinfunction "~{VALID2}_!VALID2") (pintype "bidirectional"))
    )
    (net (code "62") (name "OV1") (class "Default")
      (node (ref "R23") (pin "1") (pinfunction "1_1") (pintype "passive"))
      (node (ref "R24") (pin "2") (pinfunction "2_2") (pintype "passive"))
      (node (ref "U5") (pin "OV1") (pinfunction "OV1_OV1") (pintype "bidirectional"))
    )
    (net (code "63") (name "OV2") (class "Default")
      (node (ref "R26") (pin "1") (pinfunction "1_1") (pintype "passive"))
      (node (ref "R27") (pin "2") (pinfunction "2_2") (pintype "passive"))
      (node (ref "U5") (pin "OV2") (pinfunction "OV2_OV2") (pintype "bidirectional"))
    )
    (net (code "64") (name "POWER_BOARD") (class "Default")
      (node (ref "J8") (pin "1") (pinfunction "KL_1") (pintype "passive"))
      (node (ref "R12") (pin "P$1") (pinfunction "1_P$1") (pintype "passive"))
      (node (ref "U2") (pin "1") (pinfunction "IN-3_1") (pintype "input"))
      (node (ref "U2") (pin "14") (pinfunction "IN-2_14") (pintype "input"))
    )
    (net (code "65") (name "PV_OUT") (class "Default")
      (node (ref "U1") (pin "10") (pinfunction "PV_10") (pintype "output"))
      (node (ref "U2") (pin "10") (pinfunction "PV_10") (pintype "output"))
      (node (ref "U3") (pin "7") (pinfunction "7/RX3_7") (pintype "bidirectional"))
    )
    (net (code "66") (name "SCL") (class "Default")
      (node (ref "JP6") (pin "5") (pinfunction "5_5") (pintype "passive"))
      (node (ref "JP6") (pin "6") (pinfunction "6_6") (pintype "passive"))
      (node (ref "R14") (pin "2") (pinfunction "2_2") (pintype "passive"))
      (node (ref "U1") (pin "6") (pinfunction "SCL_6") (pintype "input"))
      (node (ref "U2") (pin "6") (pinfunction "SCL_6") (pintype "input"))
      (node (ref "U3") (pin "19/A5") (pinfunction "19/A5/T/SCL0_19/A5") (pintype "bidirectional"))
    )
    (net (code "67") (name "SDA") (class "Default")
      (node (ref "JP6") (pin "3") (pinfunction "3_3") (pintype "passive"))
      (node (ref "JP6") (pin "4") (pinfunction "4_4") (pintype "passive"))
      (node (ref "R15") (pin "2") (pinfunction "2_2") (pintype "passive"))
      (node (ref "U1") (pin "7") (pinfunction "SDA_7") (pintype "bidirectional"))
      (node (ref "U2") (pin "7") (pinfunction "SDA_7") (pintype "bidirectional"))
      (node (ref "U3") (pin "18/A4") (pinfunction "18/A4/T/SDA0_18/A4") (pintype "bidirectional"))
    )
    (net (code "68") (name "TC_OUT") (class "Default")
      (node (ref "U1") (pin "13") (pinfunction "TC_13") (pintype "output"))
      (node (ref "U2") (pin "13") (pinfunction "TC_13") (pintype "output"))
      (node (ref "U3") (pin "8") (pinfunction "8/TX3_8") (pintype "bidirectional"))
    )
    (net (code "69") (name "UV1") (class "Default")
      (node (ref "R22") (pin "1") (pinfunction "1_1") (pintype "passive"))
      (node (ref "R23") (pin "2") (pinfunction "2_2") (pintype "passive"))
      (node (ref "U5") (pin "UV1") (pinfunction "UV1_UV1") (pintype "bidirectional"))
    )
    (net (code "70") (name "UV2") (class "Default")
      (node (ref "R25") (pin "1") (pinfunction "1_1") (pintype "passive"))
      (node (ref "R26") (pin "2") (pinfunction "2_2") (pintype "passive"))
      (node (ref "U5") (pin "UV2") (pinfunction "UV2_UV2") (pintype "bidirectional"))
    )
    (net (code "71") (name "VIN") (class "Default")
      (node (ref "C4") (pin "1") (pinfunction "1_1") (pintype "passive"))
      (node (ref "JP4") (pin "1") (pinfunction "1_1") (pintype "passive"))
      (node (ref "U3") (pin "VIN") (pinfunction "VIN_VIN") (pintype "power_in"))
      (node (ref "U4") (pin "3") (pinfunction "VCC_3") (pintype "bidirectional"))
    )
    (net (code "72") (name "VS1") (class "Default")
      (node (ref "C9") (pin "1") (pinfunction "1_1") (pintype "passive"))
      (node (ref "Q10") (pin "S@1") (pinfunction "S_S@1") (pintype "passive"))
      (node (ref "Q10") (pin "S@2") (pinfunction "S_S@2") (pintype "passive"))
      (node (ref "Q10") (pin "S@3") (pinfunction "S_S@3") (pintype "passive"))
      (node (ref "Q11") (pin "S@1") (pinfunction "S_S@1") (pintype "passive"))
      (node (ref "Q11") (pin "S@2") (pinfunction "S_S@2") (pintype "passive"))
      (node (ref "Q11") (pin "S@3") (pinfunction "S_S@3") (pintype "passive"))
      (node (ref "U5") (pin "VS1") (pinfunction "VS1_VS1") (pintype "bidirectional"))
    )
    (net (code "73") (name "VS2") (class "Default")
      (node (ref "C10") (pin "1") (pinfunction "1_1") (pintype "passive"))
      (node (ref "Q12") (pin "S@1") (pinfunction "S_S@1") (pintype "passive"))
      (node (ref "Q12") (pin "S@2") (pinfunction "S_S@2") (pintype "passive"))
      (node (ref "Q12") (pin "S@3") (pinfunction "S_S@3") (pintype "passive"))
      (node (ref "Q13") (pin "S@1") (pinfunction "S_S@1") (pintype "passive"))
      (node (ref "Q13") (pin "S@2") (pinfunction "S_S@2") (pintype "passive"))
      (node (ref "Q13") (pin "S@3") (pinfunction "S_S@3") (pintype "passive"))
      (node (ref "U5") (pin "VS2") (pinfunction "VS2_VS2") (pintype "bidirectional"))
    )
    (net (code "74") (name "WALL") (class "Default")
      (node (ref "C7") (pin "1") (pinfunction "1_1") (pintype "passive"))
      (node (ref "J9") (pin "2") (pinfunction "KL1_2") (pintype "passive"))
      (node (ref "Q10") (pin "D@1") (pinfunction "D_D@1") (pintype "passive"))
      (node (ref "Q10") (pin "D@2") (pinfunction "D_D@2") (pintype "passive"))
      (node (ref "Q10") (pin "D@3") (pinfunction "D_D@3") (pintype "passive"))
      (node (ref "Q10") (pin "D@4") (pinfunction "D_D@4") (pintype "passive"))
      (node (ref "Q10") (pin "D@5") (pinfunction "D_D@5") (pintype "passive"))
      (node (ref "R22") (pin "2") (pinfunction "2_2") (pintype "passive"))
      (node (ref "U5") (pin "V1") (pinfunction "V1_V1") (pintype "bidirectional"))
    )
    (net (code "75") (name "WARNING_OUT") (class "Default")
      (node (ref "U1") (pin "8") (pinfunction "WARNING_8") (pintype "output"))
      (node (ref "U2") (pin "8") (pinfunction "WARNING_8") (pintype "output"))
      (node (ref "U3") (pin "10") (pinfunction "10/TX2/PWM_10") (pintype "bidirectional"))
    )
    (net (code "76") (name "unconnected-(U2-IN+3-Pad2)") (class "Default")
      (node (ref "U2") (pin "2") (pinfunction "IN+3_2") (pintype "input"))
    )
    (net (code "77") (name "unconnected-(U3-0{slash}RX1{slash}T-Pad0)") (class "Default")
      (node (ref "U3") (pin "0") (pinfunction "0/RX1/T_0") (pintype "bidirectional"))
    )
    (net (code "78") (name "unconnected-(U3-1{slash}TX1{slash}T-Pad1)") (class "Default")
      (node (ref "U3") (pin "1") (pinfunction "1/TX1/T_1") (pintype "bidirectional"))
    )
    (net (code "79") (name "unconnected-(U3-5{slash}PWM-Pad5)") (class "Default")
      (node (ref "U3") (pin "5") (pinfunction "5/PWM_5") (pintype "bidirectional"))
    )
    (net (code "80") (name "unconnected-(U3-6{slash}PWM-Pad6)") (class "Default")
      (node (ref "U3") (pin "6") (pinfunction "6/PWM_6") (pintype "bidirectional"))
    )
    (net (code "81") (name "unconnected-(U3-11{slash}MOSI-Pad11)") (class "Default")
      (node (ref "U3") (pin "11") (pinfunction "11/MOSI_11") (pintype "bidirectional"))
    )
    (net (code "82") (name "unconnected-(U3-12{slash}MISO-Pad12)") (class "Default")
      (node (ref "U3") (pin "12") (pinfunction "12/MISO_12") (pintype "bidirectional"))
    )
    (net (code "83") (name "unconnected-(U3-13{slash}SCK{slash}LED-Pad13)") (class "Default")
      (node (ref "U3") (pin "13") (pinfunction "13/SCK/LED_13") (pintype "bidirectional"))
    )
    (net (code "84") (name "unconnected-(U3-15{slash}A1{slash}T-Pad15{slash}A1)") (class "Default")
      (node (ref "U3") (pin "15/A1") (pinfunction "15/A1/T_15/A1") (pintype "bidirectional"))
    )
    (net (code "85") (name "unconnected-(U3-16{slash}A2{slash}T-Pad16{slash}A2)") (class "Default")
      (node (ref "U3") (pin "16/A2") (pinfunction "16/A2/T_16/A2") (pintype "bidirectional"))
    )
    (net (code "86") (name "unconnected-(U3-17{slash}A3{slash}T-Pad17{slash}A3)") (class "Default")
      (node (ref "U3") (pin "17/A3") (pinfunction "17/A3/T_17/A3") (pintype "bidirectional"))
    )
    (net (code "87") (name "unconnected-(U3-20{slash}A6{slash}PWM-Pad20{slash}A6)") (class "Default")
      (node (ref "U3") (pin "20/A6") (pinfunction "20/A6/PWM_20/A6") (pintype "bidirectional"))
    )
    (net (code "88") (name "unconnected-(U3-21{slash}A7{slash}PWM-Pad21{slash}A7)") (class "Default")
      (node (ref "U3") (pin "21/A7") (pinfunction "21/A7/PWM_21/A7") (pintype "bidirectional"))
    )
    (net (code "89") (name "unconnected-(U3-22{slash}A8{slash}T{slash}PWM-Pad22{slash}A8)") (class "Default")
      (node (ref "U3") (pin "22/A8") (pinfunction "22/A8/T/PWM_22/A8") (pintype "bidirectional"))
    )
    (net (code "90") (name "unconnected-(U3-23{slash}A9{slash}T{slash}PWM-Pad23{slash}A9)") (class "Default")
      (node (ref "U3") (pin "23/A9") (pinfunction "23/A9/T/PWM_23/A9") (pintype "bidirectional"))
    )
    (net (code "91") (name "unconnected-(U3-Pad2)") (class "Default")
      (node (ref "U3") (pin "2") (pinfunction "2_2") (pintype "bidirectional"))
    )
    (net (code "92") (name "unconnected-(U3-Pad14{slash}A0)") (class "Default")
      (node (ref "U3") (pin "14/A0") (pinfunction "14/A0_14/A0") (pintype "bidirectional"))
    )
    (net (code "93") (name "unconnected-(U5-PadCAS)") (class "Default")
      (node (ref "U5") (pin "CAS") (pinfunction "CAS_CAS") (pintype "bidirectional"))
    )
  )
)
